# Motores_Bluetoothv4.net
KiCad netlist of a schematic drawn in EAGLE
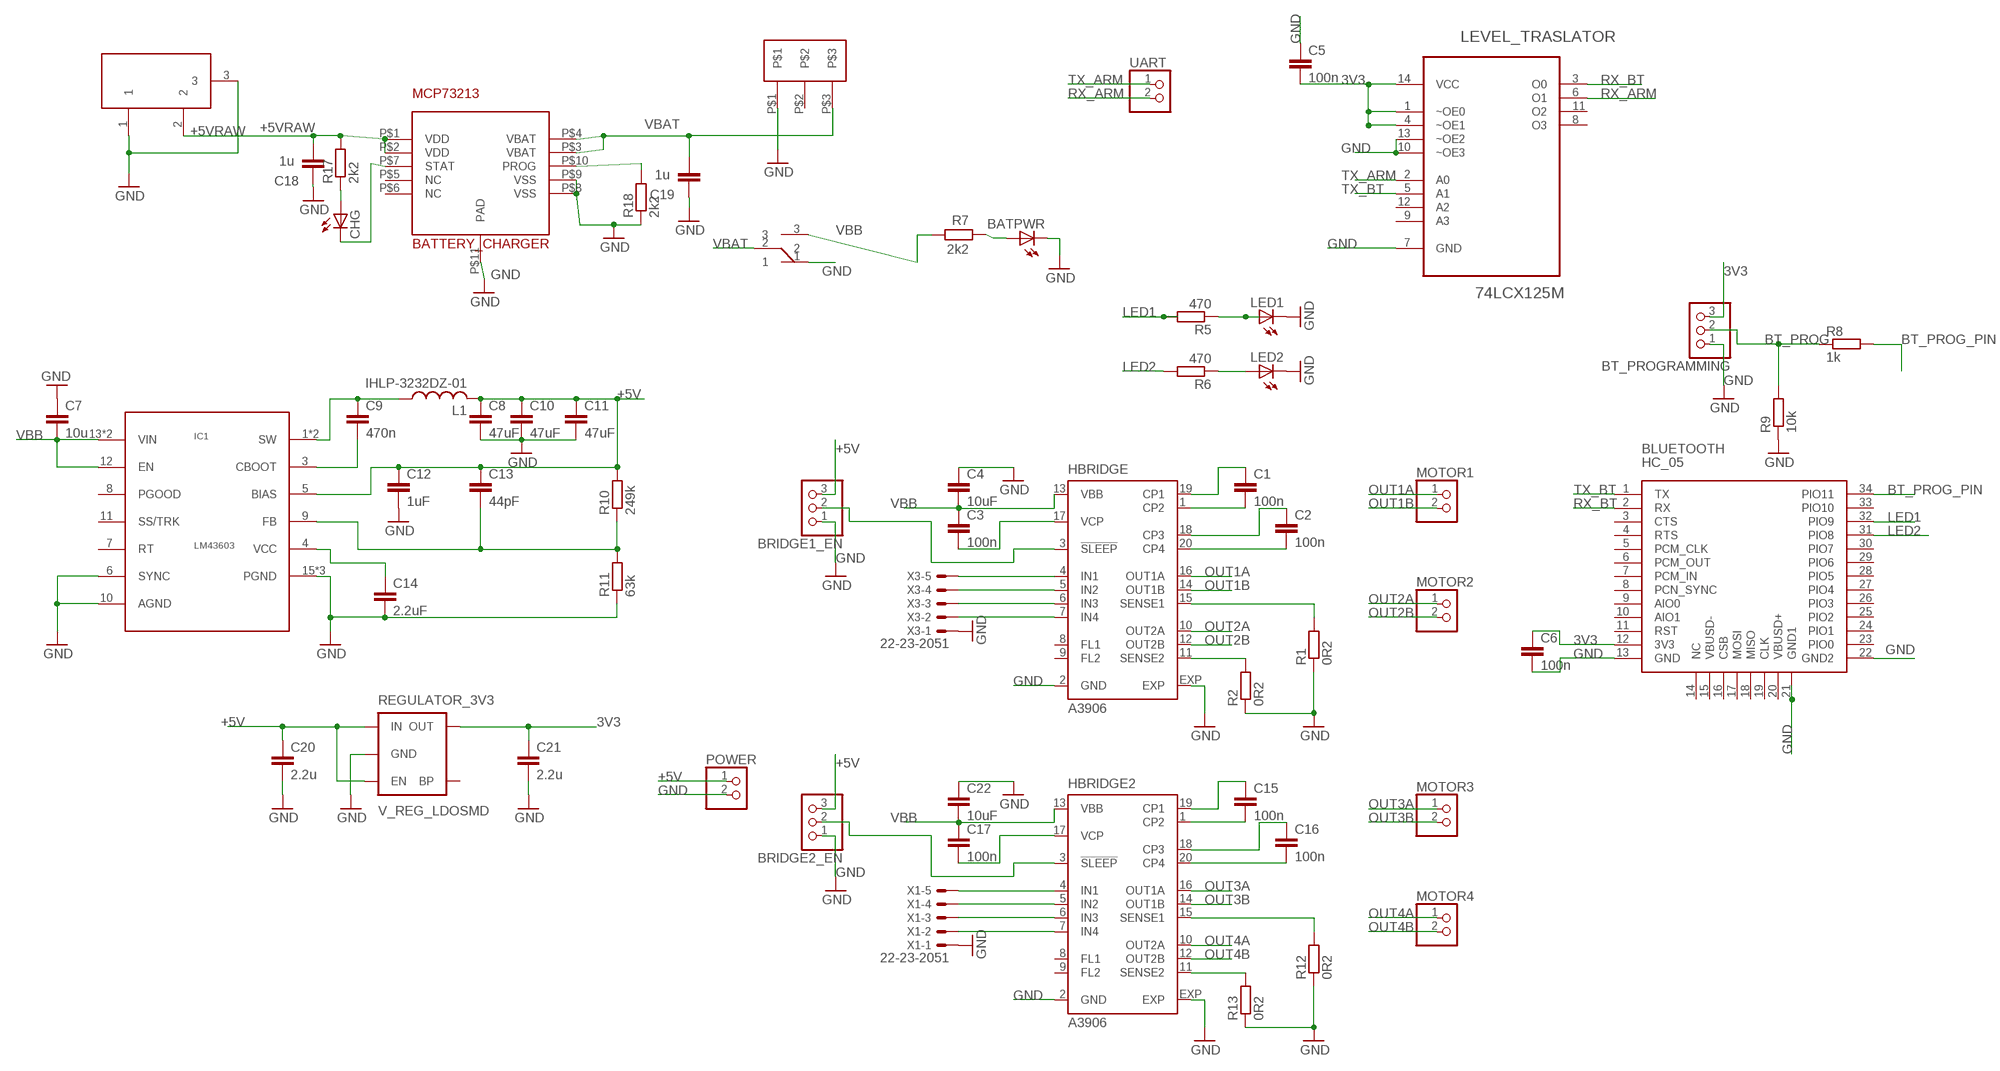
[diagram p0: schematic, sheet 1]

(export (version "E")
  (design (tool "Eeschema 10.0.6"))
  (components
    (comp (ref "BATPWR")
      (value "LEDCHIPLED_0603")
      (footprint "eagle-import:CHIPLED_0603")
      (libsource (lib "eagle-import") (part "LEDCHIPLED_0603"))
    )
    (comp (ref "BATTERY_CHARGER")
      (value "MCP73213")
      (footprint "eagle-import:DFN103X3")
      (libsource (lib "eagle-import") (part "MCP73213"))
    )
    (comp (ref "BLUETOOTH")
      (value "HC_05")
      (footprint "eagle-import:BLUETOOTH_SMD")
      (libsource (lib "eagle-import") (part "HC_05"))
    )
    (comp (ref "BRIDGE1_EN")
      (value "PINHD-1X3ROUND")
      (footprint "eagle-import:1X03ROUND")
      (libsource (lib "eagle-import") (part "PINHD-1X3ROUND"))
    )
    (comp (ref "BRIDGE2_EN")
      (value "PINHD-1X3ROUND")
      (footprint "eagle-import:1X03ROUND")
      (libsource (lib "eagle-import") (part "PINHD-1X3ROUND"))
    )
    (comp (ref "BT_PROGRAMMING")
      (value "PINHD-1X3ROUND")
      (footprint "eagle-import:1X03ROUND")
      (libsource (lib "eagle-import") (part "PINHD-1X3ROUND"))
    )
    (comp (ref "C1")
      (value "100n")
      (footprint "eagle-import:C0603")
      (libsource (lib "eagle-import") (part "C-EUC0603"))
    )
    (comp (ref "C2")
      (value "100n")
      (footprint "eagle-import:C0603")
      (libsource (lib "eagle-import") (part "C-EUC0603"))
    )
    (comp (ref "C3")
      (value "100n")
      (footprint "eagle-import:C0603")
      (libsource (lib "eagle-import") (part "C-EUC0603"))
    )
    (comp (ref "C4")
      (value "10uF")
      (footprint "eagle-import:C0805")
      (libsource (lib "eagle-import") (part "C-EUC0805"))
    )
    (comp (ref "C5")
      (value "100n")
      (footprint "eagle-import:C0603")
      (libsource (lib "eagle-import") (part "C-EUC0603"))
    )
    (comp (ref "C6")
      (value "100n")
      (footprint "eagle-import:C0603")
      (libsource (lib "eagle-import") (part "C-EUC0603"))
    )
    (comp (ref "C7")
      (value "10u")
      (footprint "eagle-import:C1206")
      (libsource (lib "eagle-import") (part "C-EUC1206"))
    )
    (comp (ref "C8")
      (value "47uF")
      (footprint "eagle-import:C1210")
      (libsource (lib "eagle-import") (part "C-EUC1210"))
    )
    (comp (ref "C9")
      (value "470n")
      (footprint "eagle-import:C0603")
      (libsource (lib "eagle-import") (part "C-EUC0603"))
    )
    (comp (ref "C10")
      (value "47uF")
      (footprint "eagle-import:C1210")
      (libsource (lib "eagle-import") (part "C-EUC1210"))
    )
    (comp (ref "C11")
      (value "47uF")
      (footprint "eagle-import:C1210")
      (libsource (lib "eagle-import") (part "C-EUC1210"))
    )
    (comp (ref "C12")
      (value "1uF")
      (footprint "eagle-import:C0805")
      (libsource (lib "eagle-import") (part "C-EUC0805"))
    )
    (comp (ref "C13")
      (value "44pF")
      (footprint "eagle-import:C0603")
      (libsource (lib "eagle-import") (part "C-EUC0603"))
    )
    (comp (ref "C14")
      (value "2.2uF")
      (footprint "eagle-import:C0805")
      (libsource (lib "eagle-import") (part "C-EUC0805"))
    )
    (comp (ref "C15")
      (value "100n")
      (footprint "eagle-import:C0603")
      (libsource (lib "eagle-import") (part "C-EUC0603"))
    )
    (comp (ref "C16")
      (value "100n")
      (footprint "eagle-import:C0603")
      (libsource (lib "eagle-import") (part "C-EUC0603"))
    )
    (comp (ref "C17")
      (value "100n")
      (footprint "eagle-import:C0603")
      (libsource (lib "eagle-import") (part "C-EUC0603"))
    )
    (comp (ref "C18")
      (value "1u")
      (footprint "eagle-import:C0603")
      (libsource (lib "eagle-import") (part "C-EUC0603"))
    )
    (comp (ref "C19")
      (value "1u")
      (footprint "eagle-import:C0603")
      (libsource (lib "eagle-import") (part "C-EUC0603"))
    )
    (comp (ref "C20")
      (value "2.2u")
      (footprint "eagle-import:C0603K")
      (libsource (lib "eagle-import") (part "C-EUC0603K"))
    )
    (comp (ref "C21")
      (value "2.2u")
      (footprint "eagle-import:C0603K")
      (libsource (lib "eagle-import") (part "C-EUC0603K"))
    )
    (comp (ref "C22")
      (value "10uF")
      (footprint "eagle-import:C0805")
      (libsource (lib "eagle-import") (part "C-EUC0805"))
    )
    (comp (ref "CHG")
      (value "LEDCHIPLED_0603")
      (footprint "eagle-import:CHIPLED_0603")
      (libsource (lib "eagle-import") (part "LEDCHIPLED_0603"))
    )
    (comp (ref "HBRIDGE")
      (value "A3906")
      (footprint "eagle-import:QFN20")
      (libsource (lib "eagle-import") (part "A3906"))
    )
    (comp (ref "HBRIDGE2")
      (value "A3906")
      (footprint "eagle-import:QFN20")
      (libsource (lib "eagle-import") (part "A3906"))
    )
    (comp (ref "IC1")
      (value "LM43603")
      (footprint "eagle-import:PW_R-PDSO-G16")
      (libsource (lib "eagle-import") (part "LM43603"))
    )
    (comp (ref "L1")
      (value "IHLP-3232DZ-01")
      (footprint "eagle-import:IHLP-3232DZ-01")
      (libsource (lib "eagle-import") (part "IHLP-3232DZ-01"))
    )
    (comp (ref "LED1")
      (value "LEDCHIP-LED0603")
      (footprint "eagle-import:CHIP-LED0603")
      (libsource (lib "eagle-import") (part "LEDCHIP-LED0603"))
    )
    (comp (ref "LED2")
      (value "LEDCHIP-LED0603")
      (footprint "eagle-import:CHIP-LED0603")
      (libsource (lib "eagle-import") (part "LEDCHIP-LED0603"))
    )
    (comp (ref "LEVEL_TRASLATOR")
      (value "74LCX125M")
      (footprint "eagle-import:SOIC127P600X175-14N")
      (libsource (lib "eagle-import") (part "74LCX125M"))
    )
    (comp (ref "MOTOR1")
      (value "PINHD-1X2ROUND")
      (footprint "eagle-import:1X02ROUND")
      (libsource (lib "eagle-import") (part "PINHD-1X2ROUND"))
    )
    (comp (ref "MOTOR2")
      (value "PINHD-1X2ROUND")
      (footprint "eagle-import:1X02ROUND")
      (libsource (lib "eagle-import") (part "PINHD-1X2ROUND"))
    )
    (comp (ref "MOTOR3")
      (value "PINHD-1X2ROUND")
      (footprint "eagle-import:1X02ROUND")
      (libsource (lib "eagle-import") (part "PINHD-1X2ROUND"))
    )
    (comp (ref "MOTOR4")
      (value "PINHD-1X2ROUND")
      (footprint "eagle-import:1X02ROUND")
      (libsource (lib "eagle-import") (part "PINHD-1X2ROUND"))
    )
    (comp (ref "POWER")
      (value "PINHD-1X2ROUND")
      (footprint "eagle-import:1X02ROUND")
      (libsource (lib "eagle-import") (part "PINHD-1X2ROUND"))
    )
    (comp (ref "R1")
      (value "0R2")
      (footprint "eagle-import:R0805")
      (libsource (lib "eagle-import") (part "R-EU_R0805"))
    )
    (comp (ref "R2")
      (value "0R2")
      (footprint "eagle-import:R0805")
      (libsource (lib "eagle-import") (part "R-EU_R0805"))
    )
    (comp (ref "R5")
      (value "470")
      (footprint "eagle-import:R0603")
      (libsource (lib "eagle-import") (part "R-EU_R0603"))
    )
    (comp (ref "R6")
      (value "470")
      (footprint "eagle-import:R0603")
      (libsource (lib "eagle-import") (part "R-EU_R0603"))
    )
    (comp (ref "R7")
      (value "2k2")
      (footprint "eagle-import:R0603")
      (libsource (lib "eagle-import") (part "R-EU_R0603"))
    )
    (comp (ref "R8")
      (value "1k")
      (footprint "eagle-import:R0603")
      (libsource (lib "eagle-import") (part "R-EU_R0603"))
    )
    (comp (ref "R9")
      (value "10k")
      (footprint "eagle-import:R0603")
      (libsource (lib "eagle-import") (part "R-EU_R0603"))
    )
    (comp (ref "R10")
      (value "249k")
      (footprint "eagle-import:R0603")
      (libsource (lib "eagle-import") (part "R-EU_R0603"))
    )
    (comp (ref "R11")
      (value "63k")
      (footprint "eagle-import:R0603")
      (libsource (lib "eagle-import") (part "R-EU_R0603"))
    )
    (comp (ref "R12")
      (value "0R2")
      (footprint "eagle-import:R0805")
      (libsource (lib "eagle-import") (part "R-EU_R0805"))
    )
    (comp (ref "R13")
      (value "0R2")
      (footprint "eagle-import:R0805")
      (libsource (lib "eagle-import") (part "R-EU_R0805"))
    )
    (comp (ref "R17")
      (value "2k2")
      (footprint "eagle-import:R0603")
      (libsource (lib "eagle-import") (part "R-EU_R0603"))
    )
    (comp (ref "R18")
      (value "2k2")
      (footprint "eagle-import:R0603")
      (libsource (lib "eagle-import") (part "R-EU_R0603"))
    )
    (comp (ref "REGULATOR_3V3")
      (value "V_REG_LDOSMD")
      (footprint "eagle-import:SOT23-5")
      (libsource (lib "eagle-import") (part "V_REG_LDOSMD"))
    )
    (comp (ref "U$1")
      (value "100SP1T1B4M2QE")
      (footprint "eagle-import:100SP1T1B4M2QE")
      (libsource (lib "eagle-import") (part "100SP1T1B4M2QE"))
    )
    (comp (ref "U$3")
      (value "JST-XHA-3")
      (footprint "eagle-import:JST-XHA-3")
      (libsource (lib "eagle-import") (part "JST-XHA-3"))
    )
    (comp (ref "UART")
      (value "PINHD-1X2ROUND")
      (footprint "eagle-import:1X02ROUND")
      (libsource (lib "eagle-import") (part "PINHD-1X2ROUND"))
    )
    (comp (ref "X1")
      (value "22-23-2051")
      (footprint "eagle-import:22-23-2051")
      (fields (field (name "MF") "MOLEX"))
      (libsource (lib "eagle-import") (part "22-23-2051"))
    )
    (comp (ref "X2")
      (value "DC21MMX")
      (footprint "eagle-import:DC-21MM")
      (libsource (lib "eagle-import") (part "DC21MMX"))
    )
    (comp (ref "X3")
      (value "22-23-2051")
      (footprint "eagle-import:22-23-2051")
      (fields (field (name "MF") "MOLEX"))
      (libsource (lib "eagle-import") (part "22-23-2051"))
    )
  )
  (nets
    (net (code "1") (name "/+5V") (class "Default")
      (node (ref "BRIDGE1_EN") (pin "3") (pinfunction "3_3") (pintype "passive"))
      (node (ref "BRIDGE2_EN") (pin "3") (pinfunction "3_3") (pintype "passive"))
      (node (ref "C10") (pin "1") (pinfunction "1_1") (pintype "passive"))
      (node (ref "C11") (pin "1") (pinfunction "1_1") (pintype "passive"))
      (node (ref "C12") (pin "1") (pinfunction "1_1") (pintype "passive"))
      (node (ref "C13") (pin "1") (pinfunction "1_1") (pintype "passive"))
      (node (ref "C20") (pin "1") (pinfunction "1_1") (pintype "passive"))
      (node (ref "C8") (pin "1") (pinfunction "1_1") (pintype "passive"))
      (node (ref "IC1") (pin "5") (pinfunction "BIAS_5") (pintype "bidirectional"))
      (node (ref "L1") (pin "P$2") (pinfunction "2_P$2") (pintype "passive"))
      (node (ref "POWER") (pin "1") (pinfunction "1_1") (pintype "passive"))
      (node (ref "R10") (pin "2") (pinfunction "2_2") (pintype "passive"))
      (node (ref "REGULATOR_3V3") (pin "1") (pinfunction "IN_1") (pintype "input"))
      (node (ref "REGULATOR_3V3") (pin "3") (pinfunction "EN_3") (pintype "input"))
    )
    (net (code "2") (name "/+5VRAW") (class "Default")
      (node (ref "BATTERY_CHARGER") (pin "P$1") (pinfunction "VDD_P$1") (pintype "bidirectional"))
      (node (ref "BATTERY_CHARGER") (pin "P$2") (pinfunction "VDD_P$2") (pintype "bidirectional"))
      (node (ref "C18") (pin "1") (pinfunction "1_1") (pintype "passive"))
      (node (ref "R17") (pin "2") (pinfunction "2_2") (pintype "passive"))
      (node (ref "X2") (pin "2") (pinfunction "2_2") (pintype "power_in"))
    )
    (net (code "3") (name "/3V3") (class "Default")
      (node (ref "BLUETOOTH") (pin "12") (pinfunction "3V3_12") (pintype "bidirectional"))
      (node (ref "BT_PROGRAMMING") (pin "3") (pinfunction "3_3") (pintype "passive"))
      (node (ref "C21") (pin "1") (pinfunction "1_1") (pintype "passive"))
      (node (ref "C5") (pin "2") (pinfunction "2_2") (pintype "passive"))
      (node (ref "C6") (pin "1") (pinfunction "1_1") (pintype "passive"))
      (node (ref "LEVEL_TRASLATOR") (pin "1") (pinfunction "~{OE0}_1") (pintype "input"))
      (node (ref "LEVEL_TRASLATOR") (pin "14") (pinfunction "VCC_14") (pintype "power_in"))
      (node (ref "LEVEL_TRASLATOR") (pin "4") (pinfunction "~{OE1}_4") (pintype "input"))
      (node (ref "REGULATOR_3V3") (pin "5") (pinfunction "OUT_5") (pintype "passive"))
    )
    (net (code "4") (name "/BT_PROG") (class "Default")
      (node (ref "BT_PROGRAMMING") (pin "2") (pinfunction "2_2") (pintype "passive"))
      (node (ref "R8") (pin "1") (pinfunction "1_1") (pintype "passive"))
      (node (ref "R9") (pin "2") (pinfunction "2_2") (pintype "passive"))
    )
    (net (code "5") (name "/BT_PROG_PIN") (class "Default")
      (node (ref "BLUETOOTH") (pin "34") (pinfunction "PIO11_34") (pintype "bidirectional"))
      (node (ref "R8") (pin "2") (pinfunction "2_2") (pintype "passive"))
    )
    (net (code "6") (name "/LED1") (class "Default")
      (node (ref "BLUETOOTH") (pin "32") (pinfunction "PIO9_32") (pintype "bidirectional"))
      (node (ref "R5") (pin "2") (pinfunction "2_2") (pintype "passive"))
    )
    (net (code "7") (name "/LED2") (class "Default")
      (node (ref "BLUETOOTH") (pin "31") (pinfunction "PIO8_31") (pintype "bidirectional"))
      (node (ref "R6") (pin "2") (pinfunction "2_2") (pintype "passive"))
    )
    (net (code "8") (name "/OUT1A") (class "Default")
      (node (ref "HBRIDGE") (pin "16") (pinfunction "OUT1A_16") (pintype "output"))
      (node (ref "MOTOR1") (pin "1") (pinfunction "1_1") (pintype "passive"))
    )
    (net (code "9") (name "/OUT1B") (class "Default")
      (node (ref "HBRIDGE") (pin "14") (pinfunction "OUT1B_14") (pintype "output"))
      (node (ref "MOTOR1") (pin "2") (pinfunction "2_2") (pintype "passive"))
    )
    (net (code "10") (name "/OUT2A") (class "Default")
      (node (ref "HBRIDGE") (pin "10") (pinfunction "OUT2A_10") (pintype "output"))
      (node (ref "MOTOR2") (pin "1") (pinfunction "1_1") (pintype "passive"))
    )
    (net (code "11") (name "/OUT2B") (class "Default")
      (node (ref "HBRIDGE") (pin "12") (pinfunction "OUT2B_12") (pintype "output"))
      (node (ref "MOTOR2") (pin "2") (pinfunction "2_2") (pintype "passive"))
    )
    (net (code "12") (name "/OUT3A") (class "Default")
      (node (ref "HBRIDGE2") (pin "16") (pinfunction "OUT1A_16") (pintype "output"))
      (node (ref "MOTOR3") (pin "1") (pinfunction "1_1") (pintype "passive"))
    )
    (net (code "13") (name "/OUT3B") (class "Default")
      (node (ref "HBRIDGE2") (pin "14") (pinfunction "OUT1B_14") (pintype "output"))
      (node (ref "MOTOR3") (pin "2") (pinfunction "2_2") (pintype "passive"))
    )
    (net (code "14") (name "/OUT4A") (class "Default")
      (node (ref "HBRIDGE2") (pin "10") (pinfunction "OUT2A_10") (pintype "output"))
      (node (ref "MOTOR4") (pin "1") (pinfunction "1_1") (pintype "passive"))
    )
    (net (code "15") (name "/OUT4B") (class "Default")
      (node (ref "HBRIDGE2") (pin "12") (pinfunction "OUT2B_12") (pintype "output"))
      (node (ref "MOTOR4") (pin "2") (pinfunction "2_2") (pintype "passive"))
    )
    (net (code "16") (name "/RX_ARM") (class "Default")
      (node (ref "LEVEL_TRASLATOR") (pin "6") (pinfunction "O1_6") (pintype "output"))
      (node (ref "UART") (pin "2") (pinfunction "2_2") (pintype "passive"))
    )
    (net (code "17") (name "/RX_BT") (class "Default")
      (node (ref "BLUETOOTH") (pin "2") (pinfunction "RX_2") (pintype "bidirectional"))
      (node (ref "LEVEL_TRASLATOR") (pin "3") (pinfunction "O0_3") (pintype "output"))
    )
    (net (code "18") (name "/TX_ARM") (class "Default")
      (node (ref "LEVEL_TRASLATOR") (pin "2") (pinfunction "A0_2") (pintype "input"))
      (node (ref "UART") (pin "1") (pinfunction "1_1") (pintype "passive"))
    )
    (net (code "19") (name "/TX_BT") (class "Default")
      (node (ref "BLUETOOTH") (pin "1") (pinfunction "TX_1") (pintype "bidirectional"))
      (node (ref "LEVEL_TRASLATOR") (pin "5") (pinfunction "A1_5") (pintype "input"))
    )
    (net (code "20") (name "/VBAT") (class "Default")
      (node (ref "BATTERY_CHARGER") (pin "P$3") (pinfunction "VBAT_P$3") (pintype "bidirectional"))
      (node (ref "BATTERY_CHARGER") (pin "P$4") (pinfunction "VBAT_P$4") (pintype "bidirectional"))
      (node (ref "C19") (pin "1") (pinfunction "1_1") (pintype "passive"))
      (node (ref "U$1") (pin "2") (pinfunction "2_2") (pintype "bidirectional"))
      (node (ref "U$3") (pin "P$3") (pinfunction "P$3_P$3") (pintype "bidirectional"))
    )
    (net (code "21") (name "/VBB") (class "Default")
      (node (ref "C17") (pin "1") (pinfunction "1_1") (pintype "passive"))
      (node (ref "C22") (pin "2") (pinfunction "2_2") (pintype "passive"))
      (node (ref "C3") (pin "1") (pinfunction "1_1") (pintype "passive"))
      (node (ref "C4") (pin "2") (pinfunction "2_2") (pintype "passive"))
      (node (ref "C7") (pin "2") (pinfunction "2_2") (pintype "passive"))
      (node (ref "HBRIDGE") (pin "13") (pinfunction "VBB_13") (pintype "power_in"))
      (node (ref "HBRIDGE2") (pin "13") (pinfunction "VBB_13") (pintype "power_in"))
      (node (ref "IC1") (pin "12") (pinfunction "EN_12") (pintype "bidirectional"))
      (node (ref "IC1") (pin "13") (pinfunction "VIN_13") (pintype "bidirectional"))
      (node (ref "IC1") (pin "14") (pinfunction "VIN_14") (pintype "bidirectional"))
      (node (ref "R7") (pin "1") (pinfunction "1_1") (pintype "passive"))
      (node (ref "U$1") (pin "3") (pinfunction "3_3") (pintype "bidirectional"))
    )
    (net (code "22") (name "GND") (class "Default")
      (node (ref "BATPWR") (pin "C") (pinfunction "C_C") (pintype "passive"))
      (node (ref "BATTERY_CHARGER") (pin "P$11") (pinfunction "PAD_P$11") (pintype "bidirectional"))
      (node (ref "BATTERY_CHARGER") (pin "P$8") (pinfunction "VSS_P$8") (pintype "bidirectional"))
      (node (ref "BATTERY_CHARGER") (pin "P$9") (pinfunction "VSS_P$9") (pintype "bidirectional"))
      (node (ref "BLUETOOTH") (pin "13") (pinfunction "GND_13") (pintype "bidirectional"))
      (node (ref "BLUETOOTH") (pin "21") (pinfunction "GND1_21") (pintype "bidirectional"))
      (node (ref "BLUETOOTH") (pin "22") (pinfunction "GND2_22") (pintype "bidirectional"))
      (node (ref "BRIDGE1_EN") (pin "1") (pinfunction "1_1") (pintype "passive"))
      (node (ref "BRIDGE2_EN") (pin "1") (pinfunction "1_1") (pintype "passive"))
      (node (ref "BT_PROGRAMMING") (pin "1") (pinfunction "1_1") (pintype "passive"))
      (node (ref "C10") (pin "2") (pinfunction "2_2") (pintype "passive"))
      (node (ref "C11") (pin "2") (pinfunction "2_2") (pintype "passive"))
      (node (ref "C12") (pin "2") (pinfunction "2_2") (pintype "passive"))
      (node (ref "C14") (pin "2") (pinfunction "2_2") (pintype "passive"))
      (node (ref "C18") (pin "2") (pinfunction "2_2") (pintype "passive"))
      (node (ref "C19") (pin "2") (pinfunction "2_2") (pintype "passive"))
      (node (ref "C20") (pin "2") (pinfunction "2_2") (pintype "passive"))
      (node (ref "C21") (pin "2") (pinfunction "2_2") (pintype "passive"))
      (node (ref "C22") (pin "1") (pinfunction "1_1") (pintype "passive"))
      (node (ref "C4") (pin "1") (pinfunction "1_1") (pintype "passive"))
      (node (ref "C5") (pin "1") (pinfunction "1_1") (pintype "passive"))
      (node (ref "C6") (pin "2") (pinfunction "2_2") (pintype "passive"))
      (node (ref "C7") (pin "1") (pinfunction "1_1") (pintype "passive"))
      (node (ref "C8") (pin "2") (pinfunction "2_2") (pintype "passive"))
      (node (ref "HBRIDGE") (pin "2") (pinfunction "GND_2") (pintype "power_in"))
      (node (ref "HBRIDGE") (pin "EXP") (pinfunction "EXP_EXP") (pintype "passive"))
      (node (ref "HBRIDGE2") (pin "2") (pinfunction "GND_2") (pintype "power_in"))
      (node (ref "HBRIDGE2") (pin "EXP") (pinfunction "EXP_EXP") (pintype "passive"))
      (node (ref "IC1") (pin "10") (pinfunction "AGND_10") (pintype "bidirectional"))
      (node (ref "IC1") (pin "15") (pinfunction "PGND_15") (pintype "bidirectional"))
      (node (ref "IC1") (pin "16") (pinfunction "PGND_16") (pintype "bidirectional"))
      (node (ref "IC1") (pin "6") (pinfunction "SYNC_6") (pintype "bidirectional"))
      (node (ref "IC1") (pin "TP") (pinfunction "PGND_TP") (pintype "bidirectional"))
      (node (ref "LED1") (pin "C") (pinfunction "C_C") (pintype "passive"))
      (node (ref "LED2") (pin "C") (pinfunction "C_C") (pintype "passive"))
      (node (ref "LEVEL_TRASLATOR") (pin "10") (pinfunction "~{OE3}_10") (pintype "input"))
      (node (ref "LEVEL_TRASLATOR") (pin "13") (pinfunction "~{OE2}_13") (pintype "input"))
      (node (ref "LEVEL_TRASLATOR") (pin "7") (pinfunction "GND_7") (pintype "passive"))
      (node (ref "POWER") (pin "2") (pinfunction "2_2") (pintype "passive"))
      (node (ref "R1") (pin "1") (pinfunction "1_1") (pintype "passive"))
      (node (ref "R11") (pin "1") (pinfunction "1_1") (pintype "passive"))
      (node (ref "R12") (pin "1") (pinfunction "1_1") (pintype "passive"))
      (node (ref "R13") (pin "1") (pinfunction "1_1") (pintype "passive"))
      (node (ref "R18") (pin "1") (pinfunction "1_1") (pintype "passive"))
      (node (ref "R2") (pin "1") (pinfunction "1_1") (pintype "passive"))
      (node (ref "R9") (pin "1") (pinfunction "1_1") (pintype "passive"))
      (node (ref "REGULATOR_3V3") (pin "2") (pinfunction "GND_2") (pintype "input"))
      (node (ref "U$1") (pin "1") (pinfunction "1_1") (pintype "bidirectional"))
      (node (ref "U$3") (pin "P$1") (pinfunction "P$1_P$1") (pintype "bidirectional"))
      (node (ref "X1") (pin "1") (pinfunction "S_1") (pintype "passive"))
      (node (ref "X2") (pin "1") (pinfunction "1_1") (pintype "power_in"))
      (node (ref "X2") (pin "3") (pinfunction "3_3") (pintype "power_in"))
      (node (ref "X3") (pin "1") (pinfunction "S_1") (pintype "passive"))
    )
    (net (code "23") (name "Net-(BATPWR-PadA)") (class "Default")
      (node (ref "BATPWR") (pin "A") (pinfunction "A_A") (pintype "passive"))
      (node (ref "R7") (pin "2") (pinfunction "2_2") (pintype "passive"))
    )
    (net (code "24") (name "Net-(BATTERY_CHARGER-PROG)") (class "Default")
      (node (ref "BATTERY_CHARGER") (pin "P$10") (pinfunction "PROG_P$10") (pintype "bidirectional"))
      (node (ref "R18") (pin "2") (pinfunction "2_2") (pintype "passive"))
    )
    (net (code "25") (name "Net-(BATTERY_CHARGER-STAT)") (class "Default")
      (node (ref "BATTERY_CHARGER") (pin "P$7") (pinfunction "STAT_P$7") (pintype "bidirectional"))
      (node (ref "CHG") (pin "C") (pinfunction "C_C") (pintype "passive"))
    )
    (net (code "26") (name "Net-(CHG-PadA)") (class "Default")
      (node (ref "CHG") (pin "A") (pinfunction "A_A") (pintype "passive"))
      (node (ref "R17") (pin "1") (pinfunction "1_1") (pintype "passive"))
    )
    (net (code "27") (name "Net-(HBRIDGE-CP1)") (class "Default")
      (node (ref "C1") (pin "1") (pinfunction "1_1") (pintype "passive"))
      (node (ref "HBRIDGE") (pin "19") (pinfunction "CP1_19") (pintype "passive"))
    )
    (net (code "28") (name "Net-(HBRIDGE-CP2)") (class "Default")
      (node (ref "C1") (pin "2") (pinfunction "2_2") (pintype "passive"))
      (node (ref "HBRIDGE") (pin "1") (pinfunction "CP2_1") (pintype "passive"))
    )
    (net (code "29") (name "Net-(HBRIDGE-CP3)") (class "Default")
      (node (ref "C2") (pin "1") (pinfunction "1_1") (pintype "passive"))
      (node (ref "HBRIDGE") (pin "18") (pinfunction "CP3_18") (pintype "passive"))
    )
    (net (code "30") (name "Net-(HBRIDGE-CP4)") (class "Default")
      (node (ref "C2") (pin "2") (pinfunction "2_2") (pintype "passive"))
      (node (ref "HBRIDGE") (pin "20") (pinfunction "CP4_20") (pintype "passive"))
    )
    (net (code "31") (name "Net-(HBRIDGE-IN1)") (class "Default")
      (node (ref "HBRIDGE") (pin "4") (pinfunction "IN1_4") (pintype "input"))
      (node (ref "X3") (pin "5") (pinfunction "S_5") (pintype "passive"))
    )
    (net (code "32") (name "Net-(HBRIDGE-IN2)") (class "Default")
      (node (ref "HBRIDGE") (pin "5") (pinfunction "IN2_5") (pintype "input"))
      (node (ref "X3") (pin "4") (pinfunction "S_4") (pintype "passive"))
    )
    (net (code "33") (name "Net-(HBRIDGE-IN3)") (class "Default")
      (node (ref "HBRIDGE") (pin "6") (pinfunction "IN3_6") (pintype "input"))
      (node (ref "X3") (pin "3") (pinfunction "S_3") (pintype "passive"))
    )
    (net (code "34") (name "Net-(HBRIDGE-IN4)") (class "Default")
      (node (ref "HBRIDGE") (pin "7") (pinfunction "IN4_7") (pintype "input"))
      (node (ref "X3") (pin "2") (pinfunction "S_2") (pintype "passive"))
    )
    (net (code "35") (name "Net-(HBRIDGE-SENSE1)") (class "Default")
      (node (ref "HBRIDGE") (pin "15") (pinfunction "SENSE1_15") (pintype "input"))
      (node (ref "R1") (pin "2") (pinfunction "2_2") (pintype "passive"))
    )
    (net (code "36") (name "Net-(HBRIDGE-SENSE2)") (class "Default")
      (node (ref "HBRIDGE") (pin "11") (pinfunction "SENSE2_11") (pintype "input"))
      (node (ref "R2") (pin "2") (pinfunction "2_2") (pintype "passive"))
    )
    (net (code "37") (name "Net-(HBRIDGE-VCP)") (class "Default")
      (node (ref "C3") (pin "2") (pinfunction "2_2") (pintype "passive"))
      (node (ref "HBRIDGE") (pin "17") (pinfunction "VCP_17") (pintype "passive"))
    )
    (net (code "38") (name "Net-(HBRIDGE-~{SLEEP})") (class "Default")
      (node (ref "BRIDGE1_EN") (pin "2") (pinfunction "2_2") (pintype "passive"))
      (node (ref "HBRIDGE") (pin "3") (pinfunction "~{SLEEP}_3") (pintype "input"))
    )
    (net (code "39") (name "Net-(HBRIDGE2-CP1)") (class "Default")
      (node (ref "C15") (pin "1") (pinfunction "1_1") (pintype "passive"))
      (node (ref "HBRIDGE2") (pin "19") (pinfunction "CP1_19") (pintype "passive"))
    )
    (net (code "40") (name "Net-(HBRIDGE2-CP2)") (class "Default")
      (node (ref "C15") (pin "2") (pinfunction "2_2") (pintype "passive"))
      (node (ref "HBRIDGE2") (pin "1") (pinfunction "CP2_1") (pintype "passive"))
    )
    (net (code "41") (name "Net-(HBRIDGE2-CP3)") (class "Default")
      (node (ref "C16") (pin "1") (pinfunction "1_1") (pintype "passive"))
      (node (ref "HBRIDGE2") (pin "18") (pinfunction "CP3_18") (pintype "passive"))
    )
    (net (code "42") (name "Net-(HBRIDGE2-CP4)") (class "Default")
      (node (ref "C16") (pin "2") (pinfunction "2_2") (pintype "passive"))
      (node (ref "HBRIDGE2") (pin "20") (pinfunction "CP4_20") (pintype "passive"))
    )
    (net (code "43") (name "Net-(HBRIDGE2-IN1)") (class "Default")
      (node (ref "HBRIDGE2") (pin "4") (pinfunction "IN1_4") (pintype "input"))
      (node (ref "X1") (pin "5") (pinfunction "S_5") (pintype "passive"))
    )
    (net (code "44") (name "Net-(HBRIDGE2-IN2)") (class "Default")
      (node (ref "HBRIDGE2") (pin "5") (pinfunction "IN2_5") (pintype "input"))
      (node (ref "X1") (pin "4") (pinfunction "S_4") (pintype "passive"))
    )
    (net (code "45") (name "Net-(HBRIDGE2-IN3)") (class "Default")
      (node (ref "HBRIDGE2") (pin "6") (pinfunction "IN3_6") (pintype "input"))
      (node (ref "X1") (pin "3") (pinfunction "S_3") (pintype "passive"))
    )
    (net (code "46") (name "Net-(HBRIDGE2-IN4)") (class "Default")
      (node (ref "HBRIDGE2") (pin "7") (pinfunction "IN4_7") (pintype "input"))
      (node (ref "X1") (pin "2") (pinfunction "S_2") (pintype "passive"))
    )
    (net (code "47") (name "Net-(HBRIDGE2-SENSE1)") (class "Default")
      (node (ref "HBRIDGE2") (pin "15") (pinfunction "SENSE1_15") (pintype "input"))
      (node (ref "R12") (pin "2") (pinfunction "2_2") (pintype "passive"))
    )
    (net (code "48") (name "Net-(HBRIDGE2-SENSE2)") (class "Default")
      (node (ref "HBRIDGE2") (pin "11") (pinfunction "SENSE2_11") (pintype "input"))
      (node (ref "R13") (pin "2") (pinfunction "2_2") (pintype "passive"))
    )
    (net (code "49") (name "Net-(HBRIDGE2-VCP)") (class "Default")
      (node (ref "C17") (pin "2") (pinfunction "2_2") (pintype "passive"))
      (node (ref "HBRIDGE2") (pin "17") (pinfunction "VCP_17") (pintype "passive"))
    )
    (net (code "50") (name "Net-(HBRIDGE2-~{SLEEP})") (class "Default")
      (node (ref "BRIDGE2_EN") (pin "2") (pinfunction "2_2") (pintype "passive"))
      (node (ref "HBRIDGE2") (pin "3") (pinfunction "~{SLEEP}_3") (pintype "input"))
    )
    (net (code "51") (name "Net-(IC1-CBOOT)") (class "Default")
      (node (ref "C9") (pin "2") (pinfunction "2_2") (pintype "passive"))
      (node (ref "IC1") (pin "3") (pinfunction "CBOOT_3") (pintype "bidirectional"))
    )
    (net (code "52") (name "Net-(IC1-FB)") (class "Default")
      (node (ref "C13") (pin "2") (pinfunction "2_2") (pintype "passive"))
      (node (ref "IC1") (pin "9") (pinfunction "FB_9") (pintype "bidirectional"))
      (node (ref "R10") (pin "1") (pinfunction "1_1") (pintype "passive"))
      (node (ref "R11") (pin "2") (pinfunction "2_2") (pintype "passive"))
    )
    (net (code "53") (name "Net-(IC1-VCC)") (class "Default")
      (node (ref "C14") (pin "1") (pinfunction "1_1") (pintype "passive"))
      (node (ref "IC1") (pin "4") (pinfunction "VCC_4") (pintype "bidirectional"))
    )
    (net (code "54") (name "Net-(L1-1)") (class "Default")
      (node (ref "C9") (pin "1") (pinfunction "1_1") (pintype "passive"))
      (node (ref "IC1") (pin "1") (pinfunction "SW_1") (pintype "bidirectional"))
      (node (ref "IC1") (pin "2") (pinfunction "SW_2") (pintype "bidirectional"))
      (node (ref "L1") (pin "P$1") (pinfunction "1_P$1") (pintype "passive"))
    )
    (net (code "55") (name "Net-(LED1-PadA)") (class "Default")
      (node (ref "LED1") (pin "A") (pinfunction "A_A") (pintype "passive"))
      (node (ref "R5") (pin "1") (pinfunction "1_1") (pintype "passive"))
    )
    (net (code "56") (name "Net-(LED2-PadA)") (class "Default")
      (node (ref "LED2") (pin "A") (pinfunction "A_A") (pintype "passive"))
      (node (ref "R6") (pin "1") (pinfunction "1_1") (pintype "passive"))
    )
    (net (code "57") (name "unconnected-(BATTERY_CHARGER-NC-PadP$5)") (class "Default")
      (node (ref "BATTERY_CHARGER") (pin "P$5") (pinfunction "NC_P$5") (pintype "bidirectional"))
    )
    (net (code "58") (name "unconnected-(BATTERY_CHARGER-NC-PadP$6)") (class "Default")
      (node (ref "BATTERY_CHARGER") (pin "P$6") (pinfunction "NC_P$6") (pintype "bidirectional"))
    )
    (net (code "59") (name "unconnected-(BLUETOOTH-AIO0-Pad9)") (class "Default")
      (node (ref "BLUETOOTH") (pin "9") (pinfunction "AIO0_9") (pintype "bidirectional"))
    )
    (net (code "60") (name "unconnected-(BLUETOOTH-AIO1-Pad10)") (class "Default")
      (node (ref "BLUETOOTH") (pin "10") (pinfunction "AIO1_10") (pintype "bidirectional"))
    )
    (net (code "61") (name "unconnected-(BLUETOOTH-CLK-Pad19)") (class "Default")
      (node (ref "BLUETOOTH") (pin "19") (pinfunction "CLK_19") (pintype "bidirectional"))
    )
    (net (code "62") (name "unconnected-(BLUETOOTH-CSB-Pad16)") (class "Default")
      (node (ref "BLUETOOTH") (pin "16") (pinfunction "CSB_16") (pintype "bidirectional"))
    )
    (net (code "63") (name "unconnected-(BLUETOOTH-CTS-Pad3)") (class "Default")
      (node (ref "BLUETOOTH") (pin "3") (pinfunction "CTS_3") (pintype "bidirectional"))
    )
    (net (code "64") (name "unconnected-(BLUETOOTH-MISO-Pad18)") (class "Default")
      (node (ref "BLUETOOTH") (pin "18") (pinfunction "MISO_18") (pintype "bidirectional"))
    )
    (net (code "65") (name "unconnected-(BLUETOOTH-MOSI-Pad17)") (class "Default")
      (node (ref "BLUETOOTH") (pin "17") (pinfunction "MOSI_17") (pintype "bidirectional"))
    )
    (net (code "66") (name "unconnected-(BLUETOOTH-NC-Pad14)") (class "Default")
      (node (ref "BLUETOOTH") (pin "14") (pinfunction "NC_14") (pintype "bidirectional"))
    )
    (net (code "67") (name "unconnected-(BLUETOOTH-PCM_CLK-Pad5)") (class "Default")
      (node (ref "BLUETOOTH") (pin "5") (pinfunction "PCM_CLK_5") (pintype "bidirectional"))
    )
    (net (code "68") (name "unconnected-(BLUETOOTH-PCM_IN-Pad7)") (class "Default")
      (node (ref "BLUETOOTH") (pin "7") (pinfunction "PCM_IN_7") (pintype "bidirectional"))
    )
    (net (code "69") (name "unconnected-(BLUETOOTH-PCM_OUT-Pad6)") (class "Default")
      (node (ref "BLUETOOTH") (pin "6") (pinfunction "PCM_OUT_6") (pintype "bidirectional"))
    )
    (net (code "70") (name "unconnected-(BLUETOOTH-PCN_SYNC-Pad8)") (class "Default")
      (node (ref "BLUETOOTH") (pin "8") (pinfunction "PCN_SYNC_8") (pintype "bidirectional"))
    )
    (net (code "71") (name "unconnected-(BLUETOOTH-PIO0-Pad23)") (class "Default")
      (node (ref "BLUETOOTH") (pin "23") (pinfunction "PIO0_23") (pintype "bidirectional"))
    )
    (net (code "72") (name "unconnected-(BLUETOOTH-PIO1-Pad24)") (class "Default")
      (node (ref "BLUETOOTH") (pin "24") (pinfunction "PIO1_24") (pintype "bidirectional"))
    )
    (net (code "73") (name "unconnected-(BLUETOOTH-PIO2-Pad25)") (class "Default")
      (node (ref "BLUETOOTH") (pin "25") (pinfunction "PIO2_25") (pintype "bidirectional"))
    )
    (net (code "74") (name "unconnected-(BLUETOOTH-PIO3-Pad26)") (class "Default")
      (node (ref "BLUETOOTH") (pin "26") (pinfunction "PIO3_26") (pintype "bidirectional"))
    )
    (net (code "75") (name "unconnected-(BLUETOOTH-PIO4-Pad27)") (class "Default")
      (node (ref "BLUETOOTH") (pin "27") (pinfunction "PIO4_27") (pintype "bidirectional"))
    )
    (net (code "76") (name "unconnected-(BLUETOOTH-PIO5-Pad28)") (class "Default")
      (node (ref "BLUETOOTH") (pin "28") (pinfunction "PIO5_28") (pintype "bidirectional"))
    )
    (net (code "77") (name "unconnected-(BLUETOOTH-PIO6-Pad29)") (class "Default")
      (node (ref "BLUETOOTH") (pin "29") (pinfunction "PIO6_29") (pintype "bidirectional"))
    )
    (net (code "78") (name "unconnected-(BLUETOOTH-PIO7-Pad30)") (class "Default")
      (node (ref "BLUETOOTH") (pin "30") (pinfunction "PIO7_30") (pintype "bidirectional"))
    )
    (net (code "79") (name "unconnected-(BLUETOOTH-PIO10-Pad33)") (class "Default")
      (node (ref "BLUETOOTH") (pin "33") (pinfunction "PIO10_33") (pintype "bidirectional"))
    )
    (net (code "80") (name "unconnected-(BLUETOOTH-RST-Pad11)") (class "Default")
      (node (ref "BLUETOOTH") (pin "11") (pinfunction "RST_11") (pintype "bidirectional"))
    )
    (net (code "81") (name "unconnected-(BLUETOOTH-RTS-Pad4)") (class "Default")
      (node (ref "BLUETOOTH") (pin "4") (pinfunction "RTS_4") (pintype "bidirectional"))
    )
    (net (code "82") (name "unconnected-(BLUETOOTH-VBUSD+-Pad20)") (class "Default")
      (node (ref "BLUETOOTH") (pin "20") (pinfunction "VBUSD+_20") (pintype "bidirectional"))
    )
    (net (code "83") (name "unconnected-(BLUETOOTH-VBUSD--Pad15)") (class "Default")
      (node (ref "BLUETOOTH") (pin "15") (pinfunction "VBUSD-_15") (pintype "bidirectional"))
    )
    (net (code "84") (name "unconnected-(HBRIDGE-FL1-Pad8)") (class "Default")
      (node (ref "HBRIDGE") (pin "8") (pinfunction "FL1_8") (pintype "input"))
    )
    (net (code "85") (name "unconnected-(HBRIDGE-FL2-Pad9)") (class "Default")
      (node (ref "HBRIDGE") (pin "9") (pinfunction "FL2_9") (pintype "input"))
    )
    (net (code "86") (name "unconnected-(HBRIDGE2-FL1-Pad8)") (class "Default")
      (node (ref "HBRIDGE2") (pin "8") (pinfunction "FL1_8") (pintype "input"))
    )
    (net (code "87") (name "unconnected-(HBRIDGE2-FL2-Pad9)") (class "Default")
      (node (ref "HBRIDGE2") (pin "9") (pinfunction "FL2_9") (pintype "input"))
    )
    (net (code "88") (name "unconnected-(IC1-PGOOD-Pad8)") (class "Default")
      (node (ref "IC1") (pin "8") (pinfunction "PGOOD_8") (pintype "bidirectional"))
    )
    (net (code "89") (name "unconnected-(IC1-RT-Pad7)") (class "Default")
      (node (ref "IC1") (pin "7") (pinfunction "RT_7") (pintype "bidirectional"))
    )
    (net (code "90") (name "unconnected-(IC1-SS{slash}TRK-Pad11)") (class "Default")
      (node (ref "IC1") (pin "11") (pinfunction "SS/TRK_11") (pintype "bidirectional"))
    )
    (net (code "91") (name "unconnected-(LEVEL_TRASLATOR-A2-Pad12)") (class "Default")
      (node (ref "LEVEL_TRASLATOR") (pin "12") (pinfunction "A2_12") (pintype "input"))
    )
    (net (code "92") (name "unconnected-(LEVEL_TRASLATOR-A3-Pad9)") (class "Default")
      (node (ref "LEVEL_TRASLATOR") (pin "9") (pinfunction "A3_9") (pintype "input"))
    )
    (net (code "93") (name "unconnected-(LEVEL_TRASLATOR-O2-Pad11)") (class "Default")
      (node (ref "LEVEL_TRASLATOR") (pin "11") (pinfunction "O2_11") (pintype "output"))
    )
    (net (code "94") (name "unconnected-(LEVEL_TRASLATOR-O3-Pad8)") (class "Default")
      (node (ref "LEVEL_TRASLATOR") (pin "8") (pinfunction "O3_8") (pintype "output"))
    )
    (net (code "95") (name "unconnected-(REGULATOR_3V3-BP-Pad4)") (class "Default")
      (node (ref "REGULATOR_3V3") (pin "4") (pinfunction "BP_4") (pintype "input"))
    )
    (net (code "96") (name "unconnected-(U$3-PadP$2)") (class "Default")
      (node (ref "U$3") (pin "P$2") (pinfunction "P$2_P$2") (pintype "bidirectional"))
    )
  )
)
